# ProPrj___2025-11-13.net
KiCad netlist of a schematic drawn in EasyEDA Pro
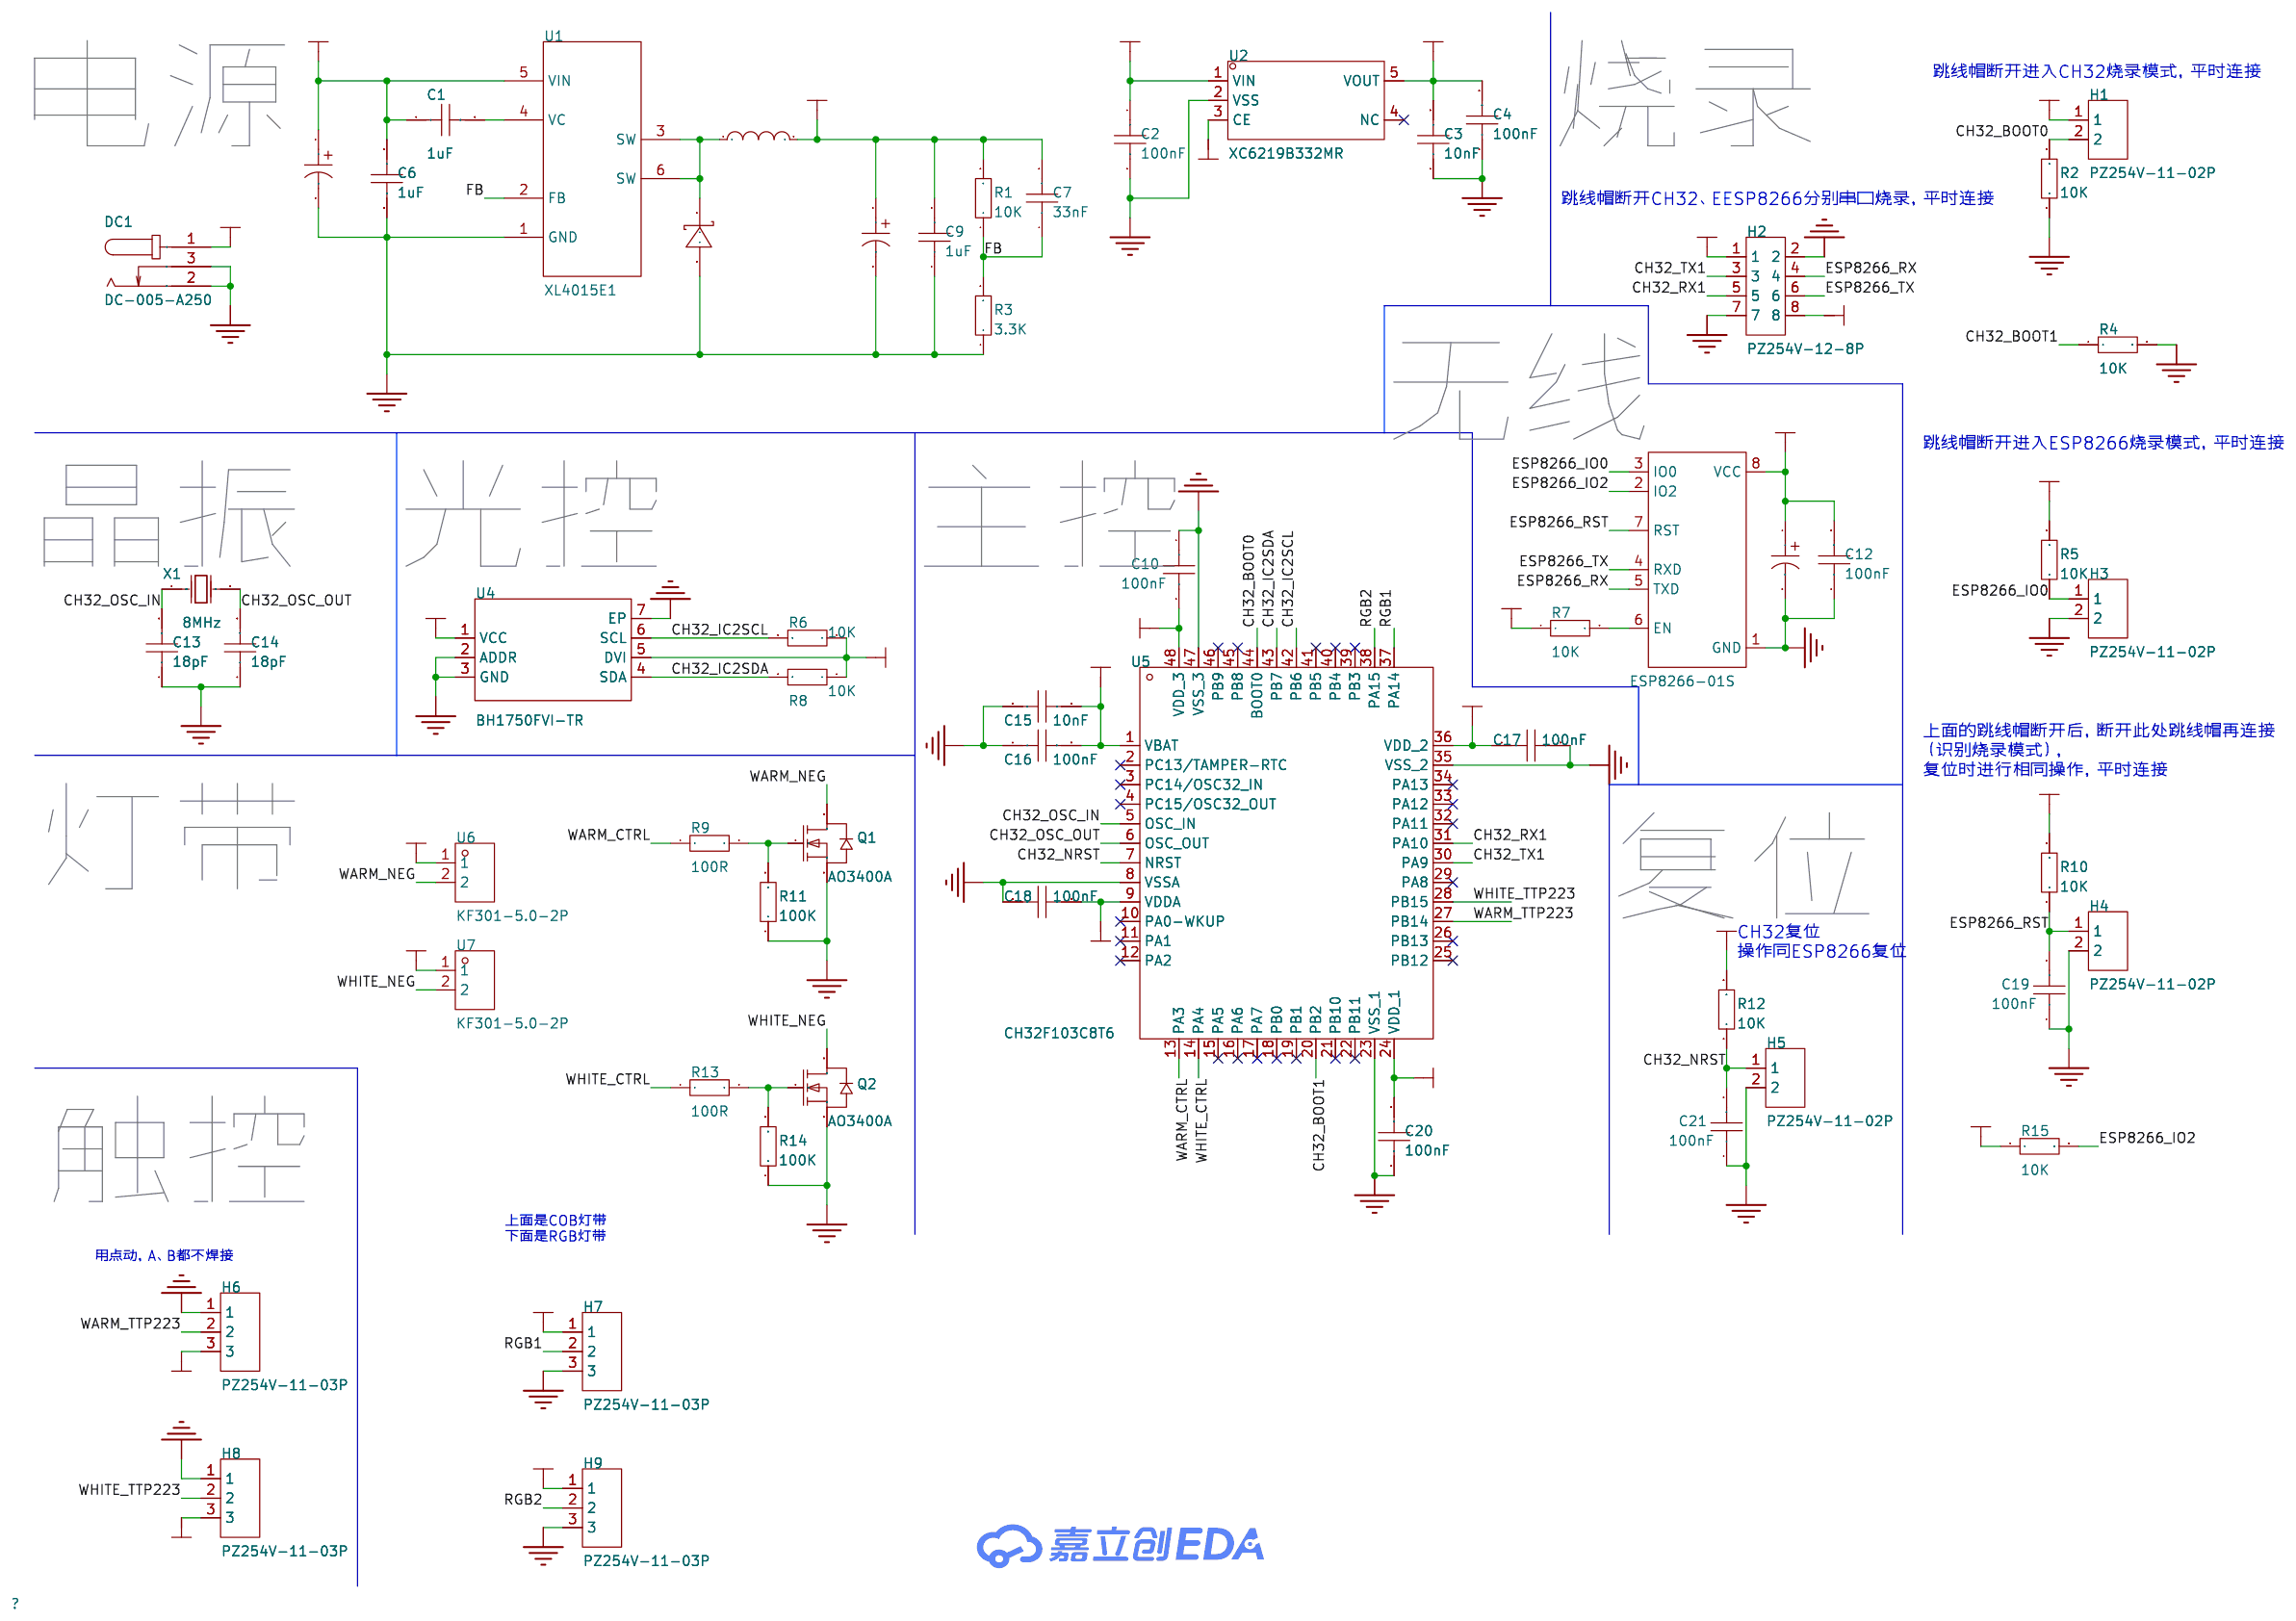
[diagram p0: schematic sheet]

(export (version "E")
  (design (tool "Eeschema 10.0.6"))
  (components
    (comp (ref "C1")
      (value "1uF")
      (footprint "easyedapro:C0805")
      (libsource (lib "easyedapro") (part "Capacitance"))
    )
    (comp (ref "C2")
      (value "100nF")
      (footprint "easyedapro:C0805")
      (libsource (lib "easyedapro") (part "Capacitance"))
    )
    (comp (ref "C3")
      (value "10nF")
      (footprint "easyedapro:C0805")
      (libsource (lib "easyedapro") (part "Capacitance"))
    )
    (comp (ref "C4")
      (value "100nF")
      (footprint "easyedapro:C0805")
      (libsource (lib "easyedapro") (part "Capacitance"))
    )
    (comp (ref "C5")
      (value "220uF")
      (footprint "easyedapro:贴片铝电解电容220uF_35V_8*10.5mm")
      (description "淘宝深圳市优信电子科技有限公司购买")
      (libsource (lib "easyedapro") (part "贴片铝电解电容220uF_35V_8*10.5mm"))
    )
    (comp (ref "C6")
      (value "1uF")
      (footprint "easyedapro:C0805")
      (libsource (lib "easyedapro") (part "Capacitance"))
    )
    (comp (ref "C7")
      (value "33nF")
      (footprint "easyedapro:C0805")
      (libsource (lib "easyedapro") (part "Capacitance"))
    )
    (comp (ref "C8")
      (value "470uF")
      (footprint "easyedapro:贴片铝电解电容470uF_10V_6.3*7.7mm")
      (description "淘宝深圳市优信电子科技有限公司购买")
      (libsource (lib "easyedapro") (part "贴片铝电解电容470uF_10V_6.3*7.7mm"))
    )
    (comp (ref "C9")
      (value "1uF")
      (footprint "easyedapro:C0805")
      (libsource (lib "easyedapro") (part "Capacitance"))
    )
    (comp (ref "C10")
      (value "100nF")
      (footprint "easyedapro:C0805")
      (libsource (lib "easyedapro") (part "Capacitance"))
    )
    (comp (ref "C11")
      (value "100uF")
      (footprint "easyedapro:贴片铝电解电容100uF_10V_5*5.4mm")
      (description "淘宝深圳市优信电子科技有限公司购买")
      (libsource (lib "easyedapro") (part "贴片铝电解电容100uF_10V_5*5.4mm"))
    )
    (comp (ref "C12")
      (value "100nF")
      (footprint "easyedapro:C0805")
      (libsource (lib "easyedapro") (part "Capacitance"))
    )
    (comp (ref "C13")
      (value "18pF")
      (footprint "easyedapro:C0805")
      (libsource (lib "easyedapro") (part "Capacitance"))
    )
    (comp (ref "C14")
      (value "18pF")
      (footprint "easyedapro:C0805")
      (libsource (lib "easyedapro") (part "Capacitance"))
    )
    (comp (ref "C15")
      (value "10nF")
      (footprint "easyedapro:C0805")
      (libsource (lib "easyedapro") (part "Capacitance"))
    )
    (comp (ref "C16")
      (value "100nF")
      (footprint "easyedapro:C0805")
      (libsource (lib "easyedapro") (part "Capacitance"))
    )
    (comp (ref "C17")
      (value "100nF")
      (footprint "easyedapro:C0805")
      (libsource (lib "easyedapro") (part "Capacitance"))
    )
    (comp (ref "C18")
      (value "100nF")
      (footprint "easyedapro:C0805")
      (libsource (lib "easyedapro") (part "Capacitance"))
    )
    (comp (ref "C19")
      (value "100nF")
      (footprint "easyedapro:C0805")
      (libsource (lib "easyedapro") (part "Capacitance"))
    )
    (comp (ref "C20")
      (value "100nF")
      (footprint "easyedapro:C0805")
      (libsource (lib "easyedapro") (part "Capacitance"))
    )
    (comp (ref "C21")
      (value "100nF")
      (footprint "easyedapro:C0805")
      (libsource (lib "easyedapro") (part "Capacitance"))
    )
    (comp (ref "D1")
      (value "SS54")
      (footprint "easyedapro:SS54SMB40V5AD0-214")
      (description "淘宝优信电子购买")
      (libsource (lib "easyedapro") (part "SS54SMB40V5AD0-214"))
    )
    (comp (ref "DC1")
      (value "DC-005-A250")
      (footprint "easyedapro:DC-IN-TH_DC-005-A250")
      (description "连接器类型:DC电源插座;安装方式:弯插;触点内径:2.5mm;触点外径:6.3mm;额定电流:3A;额定电压:30V;工作温度范围:-20°C~+70°C;")
      (fields (field (name "Manufacturer") "XUNPU(讯普)"))
      (libsource (lib "easyedapro") (part "DC-005-A250"))
    )
    (comp (ref "H1")
      (value "PZ254V-11-02P")
      (footprint "easyedapro:HDR-TH_2P-P2.54-V-M")
      (fields (field (name "Manufacturer") "XFCN(兴飞)"))
      (libsource (lib "easyedapro") (part "PZ254V-11-02P"))
    )
    (comp (ref "H2")
      (value "PZ254V-12-8P")
      (footprint "easyedapro:HDR-TH_8P-P2.54-V-M-R2-C4-S2.54")
      (fields (field (name "Manufacturer") "XFCN(兴飞)"))
      (libsource (lib "easyedapro") (part "PZ254V-12-8P"))
    )
    (comp (ref "H3")
      (value "PZ254V-11-02P")
      (footprint "easyedapro:HDR-TH_2P-P2.54-V-M")
      (fields (field (name "Manufacturer") "XFCN(兴飞)"))
      (libsource (lib "easyedapro") (part "PZ254V-11-02P"))
    )
    (comp (ref "H4")
      (value "PZ254V-11-02P")
      (footprint "easyedapro:HDR-TH_2P-P2.54-V-M")
      (fields (field (name "Manufacturer") "XFCN(兴飞)"))
      (libsource (lib "easyedapro") (part "PZ254V-11-02P"))
    )
    (comp (ref "H5")
      (value "PZ254V-11-02P")
      (footprint "easyedapro:HDR-TH_2P-P2.54-V-M")
      (fields (field (name "Manufacturer") "XFCN(兴飞)"))
      (libsource (lib "easyedapro") (part "PZ254V-11-02P"))
    )
    (comp (ref "H6")
      (value "PZ254V-11-03P")
      (footprint "easyedapro:HDR-TH_3P-P2.54-V-M")
      (fields (field (name "Manufacturer") "XFCN(兴飞)"))
      (libsource (lib "easyedapro") (part "PZ254V-11-03P_C2937625"))
    )
    (comp (ref "H7")
      (value "PZ254V-11-03P")
      (footprint "easyedapro:HDR-TH_3P-P2.54-V-M")
      (fields (field (name "Manufacturer") "XFCN(兴飞)"))
      (libsource (lib "easyedapro") (part "PZ254V-11-03P_C2937625"))
    )
    (comp (ref "H8")
      (value "PZ254V-11-03P")
      (footprint "easyedapro:HDR-TH_3P-P2.54-V-M")
      (fields (field (name "Manufacturer") "XFCN(兴飞)"))
      (libsource (lib "easyedapro") (part "PZ254V-11-03P_C2937625"))
    )
    (comp (ref "H9")
      (value "PZ254V-11-03P")
      (footprint "easyedapro:HDR-TH_3P-P2.54-V-M")
      (fields (field (name "Manufacturer") "XFCN(兴飞)"))
      (libsource (lib "easyedapro") (part "PZ254V-11-03P_C2937625"))
    )
    (comp (ref "L1")
      (value "68uH")
      (footprint "easyedapro:65125铁硅铝电感/68uH(1.0线)")
      (description "淘宝优信电子购买")
      (libsource (lib "easyedapro") (part "65125铁硅铝电感/68uH(1.0线)"))
    )
    (comp (ref "Q1")
      (value "AO3400A")
      (footprint "easyedapro:SOT-23-3_L2.9-W1.3-P1.90-LS2.4-BR")
      (fields (field (name "Manufacturer") "UMW(友台半导体)"))
      (libsource (lib "easyedapro") (part "AO3400A_C347475"))
    )
    (comp (ref "Q2")
      (value "AO3400A")
      (footprint "easyedapro:SOT-23-3_L2.9-W1.3-P1.90-LS2.4-BR")
      (fields (field (name "Manufacturer") "UMW(友台半导体)"))
      (libsource (lib "easyedapro") (part "AO3400A_C347475"))
    )
    (comp (ref "R1") (value "10K") (footprint "easyedapro:R0603") (libsource (lib "easyedapro") (part "电阻")))
    (comp (ref "R2") (value "10K") (footprint "easyedapro:R0603") (libsource (lib "easyedapro") (part "电阻")))
    (comp (ref "R3") (value "3.3K") (footprint "easyedapro:R0603") (libsource (lib "easyedapro") (part "电阻")))
    (comp (ref "R4") (value "10K") (footprint "easyedapro:R0603") (libsource (lib "easyedapro") (part "电阻")))
    (comp (ref "R5") (value "10K") (footprint "easyedapro:R0603") (libsource (lib "easyedapro") (part "电阻")))
    (comp (ref "R6") (value "10K") (footprint "easyedapro:R0603") (libsource (lib "easyedapro") (part "电阻")))
    (comp (ref "R7") (value "10K") (footprint "easyedapro:R0603") (libsource (lib "easyedapro") (part "电阻")))
    (comp (ref "R8") (value "10K") (footprint "easyedapro:R0603") (libsource (lib "easyedapro") (part "电阻")))
    (comp (ref "R9") (value "100R") (footprint "easyedapro:R0603") (libsource (lib "easyedapro") (part "电阻")))
    (comp (ref "R10") (value "10K") (footprint "easyedapro:R0603") (libsource (lib "easyedapro") (part "电阻")))
    (comp (ref "R11")
      (value "100K")
      (footprint "easyedapro:R0603")
      (libsource (lib "easyedapro") (part "电阻"))
    )
    (comp (ref "R12") (value "10K") (footprint "easyedapro:R0603") (libsource (lib "easyedapro") (part "电阻")))
    (comp (ref "R13")
      (value "100R")
      (footprint "easyedapro:R0603")
      (libsource (lib "easyedapro") (part "电阻"))
    )
    (comp (ref "R14")
      (value "100K")
      (footprint "easyedapro:R0603")
      (libsource (lib "easyedapro") (part "电阻"))
    )
    (comp (ref "R15") (value "10K") (footprint "easyedapro:R0603") (libsource (lib "easyedapro") (part "电阻")))
    (comp (ref "U1")
      (value "XL4015E1")
      (footprint "easyedapro:TO-263-5_L10.2-W8.9-P1.70-TL")
      (description "功能类型:降压型;工作电压:8V~36V;输出电压:1.25V~32V;输出电流:5A;输出类型:可调;")
      (fields (field (name "Manufacturer") "XLSEMI(芯龙)"))
      (libsource (lib "easyedapro") (part "XL4015E1"))
    )
    (comp (ref "U2")
      (value "XC6219B332MR")
      (footprint "easyedapro:SOT-23-5_L3.0-W1.7-P0.95-LS2.8-BR")
      (description "输出类型:固定;工作电压:7V;输出电压:3.3V;输出电流:300mA;电源纹波抑制比(PSRR):40dB@(1kHz);输出极性:正极;")
      (fields (field (name "Manufacturer") "UMW(友台半导体)"))
      (libsource (lib "easyedapro") (part "XC6219B332MR_C347386"))
    )
    (comp (ref "U3")
      (value "ESP8266-01S")
      (footprint "easyedapro:ESP8266ESP-01S")
      (description "淘宝深圳市优信电子科技有限公司购买")
      (libsource (lib "easyedapro") (part "ESP8266ESP-01S"))
    )
    (comp (ref "U4")
      (value "BH1750FVI-TR")
      (footprint "easyedapro:WSOF-6_L2.6-W1.6-P0.50-TL-EP")
      (description "检测颜色:-;接口类型:I2C;")
      (fields (field (name "Manufacturer") "ROHM(罗姆)"))
      (libsource (lib "easyedapro") (part "BH1750FVI-TR"))
    )
    (comp (ref "U5")
      (value "CH32F103C8T6")
      (footprint "easyedapro:LQFP-48_L7.0-W7.0-P0.50-LS9.0-BL")
      (description "CPU内核:ARM-M3;程序存储容量:64KB;RAM总容量:20KB;GPIO端口数量:37;工作电压范围:2.7V~5.5V;CPU最大主频:72MHz;程序存储器类型:-;应用领域:-;")
      (fields (field (name "Manufacturer") "WCH(南京沁恒)"))
      (libsource (lib "easyedapro") (part "CH32F103C8T6"))
    )
    (comp (ref "U6")
      (value "KF301-5.0-2P")
      (footprint "easyedapro:CONN-TH_P5.00_KF301-5.0-2P")
      (fields (field (name "Manufacturer") "KEFA(科发)"))
      (libsource (lib "easyedapro") (part "KF301-5.0-2P"))
    )
    (comp (ref "U7")
      (value "KF301-5.0-2P")
      (footprint "easyedapro:CONN-TH_P5.00_KF301-5.0-2P")
      (fields (field (name "Manufacturer") "KEFA(科发)"))
      (libsource (lib "easyedapro") (part "KF301-5.0-2P"))
    )
    (comp (ref "X1")
      (value "8MHz")
      (footprint "easyedapro:CRYSTAL-SMD_L5.0-W3.2")
      (description "晶振类型:贴片晶振;频率:8MHz;常温频差:±10ppm;负载电容:20pF;频率稳定度:±20ppm;")
      (fields (field (name "Manufacturer Part") "X50328MSB2GI") (field (name "Manufacturer") "YXC(扬兴晶振)"))
      (libsource (lib "easyedapro") (part "X50328MSB2GI"))
    )
  )
  (nets
    (net (code "1") (name "/CH32_BOOT0") (class "Default")
      (node (ref "H1") (pin "2") (pinfunction "2_2") (pintype "unspecified"))
      (node (ref "R2") (pin "2") (pinfunction "2_2") (pintype "input"))
      (node (ref "U5") (pin "44") (pinfunction "BOOT0_44") (pintype "unspecified"))
    )
    (net (code "2") (name "/CH32_BOOT1") (class "Default")
      (node (ref "R4") (pin "1") (pinfunction "1_1") (pintype "input"))
      (node (ref "U5") (pin "20") (pinfunction "PB2_20") (pintype "unspecified"))
    )
    (net (code "3") (name "/CH32_IC2SCL") (class "Default")
      (node (ref "R6") (pin "2") (pinfunction "2_2") (pintype "input"))
      (node (ref "U4") (pin "6") (pinfunction "SCL_6") (pintype "unspecified"))
      (node (ref "U5") (pin "42") (pinfunction "PB6_42") (pintype "unspecified"))
    )
    (net (code "4") (name "/CH32_IC2SDA") (class "Default")
      (node (ref "R8") (pin "2") (pinfunction "2_2") (pintype "input"))
      (node (ref "U4") (pin "4") (pinfunction "SDA_4") (pintype "unspecified"))
      (node (ref "U5") (pin "43") (pinfunction "PB7_43") (pintype "unspecified"))
    )
    (net (code "5") (name "/CH32_NRST") (class "Default")
      (node (ref "C21") (pin "2") (pinfunction "2_2") (pintype "input"))
      (node (ref "H5") (pin "1") (pinfunction "1_1") (pintype "unspecified"))
      (node (ref "R12") (pin "1") (pinfunction "1_1") (pintype "input"))
      (node (ref "U5") (pin "7") (pinfunction "NRST_7") (pintype "unspecified"))
    )
    (net (code "6") (name "/CH32_OSC_IN") (class "Default")
      (node (ref "C13") (pin "2") (pinfunction "2_2") (pintype "input"))
      (node (ref "U5") (pin "5") (pinfunction "OSC_IN_5") (pintype "unspecified"))
      (node (ref "X1") (pin "1") (pinfunction "OSC1_1") (pintype "input"))
    )
    (net (code "7") (name "/CH32_OSC_OUT") (class "Default")
      (node (ref "C14") (pin "2") (pinfunction "2_2") (pintype "input"))
      (node (ref "U5") (pin "6") (pinfunction "OSC_OUT_6") (pintype "unspecified"))
      (node (ref "X1") (pin "2") (pinfunction "OSC2_2") (pintype "input"))
    )
    (net (code "8") (name "/CH32_RX1") (class "Default")
      (node (ref "H2") (pin "5") (pinfunction "5_5") (pintype "unspecified"))
      (node (ref "U5") (pin "31") (pinfunction "PA10_31") (pintype "unspecified"))
    )
    (net (code "9") (name "/CH32_TX1") (class "Default")
      (node (ref "H2") (pin "3") (pinfunction "3_3") (pintype "unspecified"))
      (node (ref "U5") (pin "30") (pinfunction "PA9_30") (pintype "unspecified"))
    )
    (net (code "10") (name "/ESP8266_IO0") (class "Default")
      (node (ref "H3") (pin "1") (pinfunction "1_1") (pintype "unspecified"))
      (node (ref "R5") (pin "1") (pinfunction "1_1") (pintype "input"))
      (node (ref "U3") (pin "3") (pinfunction "IO0_3") (pintype "unspecified"))
    )
    (net (code "11") (name "/ESP8266_IO2") (class "Default")
      (node (ref "R15") (pin "2") (pinfunction "2_2") (pintype "input"))
      (node (ref "U3") (pin "2") (pinfunction "IO2_2") (pintype "unspecified"))
    )
    (net (code "12") (name "/ESP8266_RST") (class "Default")
      (node (ref "C19") (pin "2") (pinfunction "2_2") (pintype "input"))
      (node (ref "H4") (pin "1") (pinfunction "1_1") (pintype "unspecified"))
      (node (ref "R10") (pin "1") (pinfunction "1_1") (pintype "input"))
      (node (ref "U3") (pin "7") (pinfunction "RST_7") (pintype "unspecified"))
    )
    (net (code "13") (name "/ESP8266_RX") (class "Default")
      (node (ref "H2") (pin "4") (pinfunction "4_4") (pintype "unspecified"))
      (node (ref "U3") (pin "5") (pinfunction "TXD_5") (pintype "unspecified"))
    )
    (net (code "14") (name "/ESP8266_TX") (class "Default")
      (node (ref "H2") (pin "6") (pinfunction "6_6") (pintype "unspecified"))
      (node (ref "U3") (pin "4") (pinfunction "RXD_4") (pintype "unspecified"))
    )
    (net (code "15") (name "/FB") (class "Default")
      (node (ref "C7") (pin "1") (pinfunction "1_1") (pintype "input"))
      (node (ref "R1") (pin "1") (pinfunction "1_1") (pintype "input"))
      (node (ref "R3") (pin "2") (pinfunction "2_2") (pintype "input"))
      (node (ref "U1") (pin "2") (pinfunction "FB_2") (pintype "unspecified"))
    )
    (net (code "16") (name "/RGB1") (class "Default")
      (node (ref "H7") (pin "2") (pinfunction "2_2") (pintype "unspecified"))
      (node (ref "U5") (pin "37") (pinfunction "PA14_37") (pintype "unspecified"))
    )
    (net (code "17") (name "/RGB2") (class "Default")
      (node (ref "H9") (pin "2") (pinfunction "2_2") (pintype "unspecified"))
      (node (ref "U5") (pin "38") (pinfunction "PA15_38") (pintype "unspecified"))
    )
    (net (code "18") (name "/WARM_CTRL") (class "Default")
      (node (ref "R9") (pin "1") (pinfunction "1_1") (pintype "input"))
      (node (ref "U5") (pin "13") (pinfunction "PA3_13") (pintype "unspecified"))
    )
    (net (code "19") (name "/WARM_NEG") (class "Default")
      (node (ref "Q1") (pin "3") (pinfunction "D_3") (pintype "unspecified"))
      (node (ref "U6") (pin "2") (pinfunction "2_2") (pintype "unspecified"))
    )
    (net (code "20") (name "/WARM_TTP223") (class "Default")
      (node (ref "H6") (pin "2") (pinfunction "2_2") (pintype "unspecified"))
      (node (ref "U5") (pin "27") (pinfunction "PB14_27") (pintype "unspecified"))
    )
    (net (code "21") (name "/WHITE_CTRL") (class "Default")
      (node (ref "R13") (pin "1") (pinfunction "1_1") (pintype "input"))
      (node (ref "U5") (pin "14") (pinfunction "PA4_14") (pintype "unspecified"))
    )
    (net (code "22") (name "/WHITE_NEG") (class "Default")
      (node (ref "Q2") (pin "3") (pinfunction "D_3") (pintype "unspecified"))
      (node (ref "U7") (pin "2") (pinfunction "2_2") (pintype "unspecified"))
    )
    (net (code "23") (name "/WHITE_TTP223") (class "Default")
      (node (ref "H8") (pin "2") (pinfunction "2_2") (pintype "unspecified"))
      (node (ref "U5") (pin "28") (pinfunction "PB15_28") (pintype "unspecified"))
    )
    (net (code "24") (name "3.3V") (class "Default")
      (node (ref "C10") (pin "2") (pinfunction "2_2") (pintype "input"))
      (node (ref "C11") (pin "1") (pinfunction "1_1") (pintype "input"))
      (node (ref "C12") (pin "2") (pinfunction "2_2") (pintype "input"))
      (node (ref "C15") (pin "2") (pinfunction "2_2") (pintype "input"))
      (node (ref "C16") (pin "2") (pinfunction "2_2") (pintype "input"))
      (node (ref "C17") (pin "1") (pinfunction "1_1") (pintype "input"))
      (node (ref "C18") (pin "2") (pinfunction "2_2") (pintype "input"))
      (node (ref "C20") (pin "2") (pinfunction "2_2") (pintype "input"))
      (node (ref "C3") (pin "2") (pinfunction "2_2") (pintype "input"))
      (node (ref "C4") (pin "2") (pinfunction "2_2") (pintype "input"))
      (node (ref "H1") (pin "1") (pinfunction "1_1") (pintype "unspecified"))
      (node (ref "H2") (pin "1") (pinfunction "1_1") (pintype "unspecified"))
      (node (ref "H2") (pin "8") (pinfunction "8_8") (pintype "unspecified"))
      (node (ref "H6") (pin "3") (pinfunction "3_3") (pintype "unspecified"))
      (node (ref "H8") (pin "3") (pinfunction "3_3") (pintype "unspecified"))
      (node (ref "R10") (pin "2") (pinfunction "2_2") (pintype "input"))
      (node (ref "R12") (pin "2") (pinfunction "2_2") (pintype "input"))
      (node (ref "R15") (pin "1") (pinfunction "1_1") (pintype "input"))
      (node (ref "R5") (pin "2") (pinfunction "2_2") (pintype "input"))
      (node (ref "R6") (pin "1") (pinfunction "1_1") (pintype "input"))
      (node (ref "R7") (pin "1") (pinfunction "1_1") (pintype "input"))
      (node (ref "R8") (pin "1") (pinfunction "1_1") (pintype "input"))
      (node (ref "U2") (pin "5") (pinfunction "VOUT_5") (pintype "unspecified"))
      (node (ref "U3") (pin "8") (pinfunction "VCC_8") (pintype "unspecified"))
      (node (ref "U4") (pin "1") (pinfunction "VCC_1") (pintype "unspecified"))
      (node (ref "U4") (pin "5") (pinfunction "DVI_5") (pintype "unspecified"))
      (node (ref "U5") (pin "1") (pinfunction "VBAT_1") (pintype "unspecified"))
      (node (ref "U5") (pin "24") (pinfunction "VDD_1_24") (pintype "unspecified"))
      (node (ref "U5") (pin "36") (pinfunction "VDD_2_36") (pintype "unspecified"))
      (node (ref "U5") (pin "48") (pinfunction "VDD_3_48") (pintype "unspecified"))
      (node (ref "U5") (pin "9") (pinfunction "VDDA_9") (pintype "unspecified"))
    )
    (net (code "25") (name "5V") (class "Default")
      (node (ref "C2") (pin "1") (pinfunction "1_1") (pintype "input"))
      (node (ref "C7") (pin "2") (pinfunction "2_2") (pintype "input"))
      (node (ref "C8") (pin "1") (pinfunction "1_1") (pintype "input"))
      (node (ref "C9") (pin "2") (pinfunction "2_2") (pintype "input"))
      (node (ref "H7") (pin "1") (pinfunction "1_1") (pintype "unspecified"))
      (node (ref "H9") (pin "1") (pinfunction "1_1") (pintype "unspecified"))
      (node (ref "L1") (pin "2") (pinfunction "2_2") (pintype "unspecified"))
      (node (ref "R1") (pin "2") (pinfunction "2_2") (pintype "input"))
      (node (ref "U2") (pin "1") (pinfunction "VIN_1") (pintype "unspecified"))
      (node (ref "U2") (pin "3") (pinfunction "CE_3") (pintype "unspecified"))
    )
    (net (code "26") (name "24V") (class "Default")
      (node (ref "C1") (pin "1") (pinfunction "1_1") (pintype "input"))
      (node (ref "C5") (pin "1") (pinfunction "1_1") (pintype "input"))
      (node (ref "C6") (pin "1") (pinfunction "1_1") (pintype "input"))
      (node (ref "DC1") (pin "1") (pinfunction "1_1") (pintype "input"))
      (node (ref "U1") (pin "5") (pinfunction "VIN_5") (pintype "unspecified"))
      (node (ref "U6") (pin "1") (pinfunction "1_1") (pintype "unspecified"))
      (node (ref "U7") (pin "1") (pinfunction "1_1") (pintype "unspecified"))
    )
    (net (code "27") (name "GND") (class "Default")
      (node (ref "C10") (pin "1") (pinfunction "1_1") (pintype "input"))
      (node (ref "C11") (pin "2") (pinfunction "2_2") (pintype "input"))
      (node (ref "C12") (pin "1") (pinfunction "1_1") (pintype "input"))
      (node (ref "C13") (pin "1") (pinfunction "1_1") (pintype "input"))
      (node (ref "C14") (pin "1") (pinfunction "1_1") (pintype "input"))
      (node (ref "C15") (pin "1") (pinfunction "1_1") (pintype "input"))
      (node (ref "C16") (pin "1") (pinfunction "1_1") (pintype "input"))
      (node (ref "C17") (pin "2") (pinfunction "2_2") (pintype "input"))
      (node (ref "C18") (pin "1") (pinfunction "1_1") (pintype "input"))
      (node (ref "C19") (pin "1") (pinfunction "1_1") (pintype "input"))
      (node (ref "C2") (pin "2") (pinfunction "2_2") (pintype "input"))
      (node (ref "C20") (pin "1") (pinfunction "1_1") (pintype "input"))
      (node (ref "C21") (pin "1") (pinfunction "1_1") (pintype "input"))
      (node (ref "C3") (pin "1") (pinfunction "1_1") (pintype "input"))
      (node (ref "C4") (pin "1") (pinfunction "1_1") (pintype "input"))
      (node (ref "C5") (pin "2") (pinfunction "2_2") (pintype "input"))
      (node (ref "C6") (pin "2") (pinfunction "2_2") (pintype "input"))
      (node (ref "C8") (pin "2") (pinfunction "2_2") (pintype "input"))
      (node (ref "C9") (pin "1") (pinfunction "1_1") (pintype "input"))
      (node (ref "D1") (pin "2") (pinfunction "A_2") (pintype "unspecified"))
      (node (ref "DC1") (pin "2") (pinfunction "2_2") (pintype "input"))
      (node (ref "DC1") (pin "3") (pinfunction "3_3") (pintype "input"))
      (node (ref "H2") (pin "2") (pinfunction "2_2") (pintype "unspecified"))
      (node (ref "H2") (pin "7") (pinfunction "7_7") (pintype "unspecified"))
      (node (ref "H3") (pin "2") (pinfunction "2_2") (pintype "unspecified"))
      (node (ref "H4") (pin "2") (pinfunction "2_2") (pintype "unspecified"))
      (node (ref "H5") (pin "2") (pinfunction "2_2") (pintype "unspecified"))
      (node (ref "H6") (pin "1") (pinfunction "1_1") (pintype "unspecified"))
      (node (ref "H7") (pin "3") (pinfunction "3_3") (pintype "unspecified"))
      (node (ref "H8") (pin "1") (pinfunction "1_1") (pintype "unspecified"))
      (node (ref "H9") (pin "3") (pinfunction "3_3") (pintype "unspecified"))
      (node (ref "Q1") (pin "2") (pinfunction "S_2") (pintype "unspecified"))
      (node (ref "Q2") (pin "2") (pinfunction "S_2") (pintype "unspecified"))
      (node (ref "R11") (pin "1") (pinfunction "1_1") (pintype "input"))
      (node (ref "R14") (pin "1") (pinfunction "1_1") (pintype "input"))
      (node (ref "R2") (pin "1") (pinfunction "1_1") (pintype "input"))
      (node (ref "R3") (pin "1") (pinfunction "1_1") (pintype "input"))
      (node (ref "R4") (pin "2") (pinfunction "2_2") (pintype "input"))
      (node (ref "U1") (pin "1") (pinfunction "GND_1") (pintype "unspecified"))
      (node (ref "U2") (pin "2") (pinfunction "VSS_2") (pintype "unspecified"))
      (node (ref "U3") (pin "1") (pinfunction "GND_1") (pintype "unspecified"))
      (node (ref "U4") (pin "2") (pinfunction "ADDR_2") (pintype "unspecified"))
      (node (ref "U4") (pin "3") (pinfunction "GND_3") (pintype "unspecified"))
      (node (ref "U4") (pin "7") (pinfunction "EP_7") (pintype "unspecified"))
      (node (ref "U5") (pin "23") (pinfunction "VSS_1_23") (pintype "unspecified"))
      (node (ref "U5") (pin "35") (pinfunction "VSS_2_35") (pintype "unspecified"))
      (node (ref "U5") (pin "47") (pinfunction "VSS_3_47") (pintype "unspecified"))
      (node (ref "U5") (pin "8") (pinfunction "VSSA_8") (pintype "unspecified"))
    )
    (net (code "28") (name "Net-(D1-K)") (class "Default")
      (node (ref "D1") (pin "1") (pinfunction "K_1") (pintype "unspecified"))
      (node (ref "L1") (pin "1") (pinfunction "1_1") (pintype "unspecified"))
      (node (ref "U1") (pin "3") (pinfunction "SW_3") (pintype "unspecified"))
      (node (ref "U1") (pin "6") (pinfunction "SW_6") (pintype "unspecified"))
    )
    (net (code "29") (name "Net-(Q1-G)") (class "Default")
      (node (ref "Q1") (pin "1") (pinfunction "G_1") (pintype "unspecified"))
      (node (ref "R11") (pin "2") (pinfunction "2_2") (pintype "input"))
      (node (ref "R9") (pin "2") (pinfunction "2_2") (pintype "input"))
    )
    (net (code "30") (name "Net-(Q2-G)") (class "Default")
      (node (ref "Q2") (pin "1") (pinfunction "G_1") (pintype "unspecified"))
      (node (ref "R13") (pin "2") (pinfunction "2_2") (pintype "input"))
      (node (ref "R14") (pin "2") (pinfunction "2_2") (pintype "input"))
    )
    (net (code "31") (name "Net-(U1-VC)") (class "Default")
      (node (ref "C1") (pin "2") (pinfunction "2_2") (pintype "input"))
      (node (ref "U1") (pin "4") (pinfunction "VC_4") (pintype "unspecified"))
    )
    (net (code "32") (name "Net-(U3-EN)") (class "Default")
      (node (ref "R7") (pin "2") (pinfunction "2_2") (pintype "input"))
      (node (ref "U3") (pin "6") (pinfunction "EN_6") (pintype "unspecified"))
    )
    (net (code "33") (name "unconnected-(U2-NC-Pad4)") (class "Default")
      (node (ref "U2") (pin "4") (pinfunction "NC_4") (pintype "unspecified+no_connect"))
    )
    (net (code "34") (name "unconnected-(U5-PA0-WKUP-Pad10)") (class "Default")
      (node (ref "U5") (pin "10") (pinfunction "PA0-WKUP_10") (pintype "unspecified+no_connect"))
    )
    (net (code "35") (name "unconnected-(U5-PA1-Pad11)") (class "Default")
      (node (ref "U5") (pin "11") (pinfunction "PA1_11") (pintype "unspecified+no_connect"))
    )
    (net (code "36") (name "unconnected-(U5-PA2-Pad12)") (class "Default")
      (node (ref "U5") (pin "12") (pinfunction "PA2_12") (pintype "unspecified+no_connect"))
    )
    (net (code "37") (name "unconnected-(U5-PA5-Pad15)") (class "Default")
      (node (ref "U5") (pin "15") (pinfunction "PA5_15") (pintype "unspecified+no_connect"))
    )
    (net (code "38") (name "unconnected-(U5-PA6-Pad16)") (class "Default")
      (node (ref "U5") (pin "16") (pinfunction "PA6_16") (pintype "unspecified+no_connect"))
    )
    (net (code "39") (name "unconnected-(U5-PA7-Pad17)") (class "Default")
      (node (ref "U5") (pin "17") (pinfunction "PA7_17") (pintype "unspecified+no_connect"))
    )
    (net (code "40") (name "unconnected-(U5-PA8-Pad29)") (class "Default")
      (node (ref "U5") (pin "29") (pinfunction "PA8_29") (pintype "unspecified+no_connect"))
    )
    (net (code "41") (name "unconnected-(U5-PA11-Pad32)") (class "Default")
      (node (ref "U5") (pin "32") (pinfunction "PA11_32") (pintype "unspecified+no_connect"))
    )
    (net (code "42") (name "unconnected-(U5-PA12-Pad33)") (class "Default")
      (node (ref "U5") (pin "33") (pinfunction "PA12_33") (pintype "unspecified+no_connect"))
    )
    (net (code "43") (name "unconnected-(U5-PA13-Pad34)") (class "Default")
      (node (ref "U5") (pin "34") (pinfunction "PA13_34") (pintype "unspecified+no_connect"))
    )
    (net (code "44") (name "unconnected-(U5-PB0-Pad18)") (class "Default")
      (node (ref "U5") (pin "18") (pinfunction "PB0_18") (pintype "unspecified+no_connect"))
    )
    (net (code "45") (name "unconnected-(U5-PB1-Pad19)") (class "Default")
      (node (ref "U5") (pin "19") (pinfunction "PB1_19") (pintype "unspecified+no_connect"))
    )
    (net (code "46") (name "unconnected-(U5-PB3-Pad39)") (class "Default")
      (node (ref "U5") (pin "39") (pinfunction "PB3_39") (pintype "unspecified+no_connect"))
    )
    (net (code "47") (name "unconnected-(U5-PB4-Pad40)") (class "Default")
      (node (ref "U5") (pin "40") (pinfunction "PB4_40") (pintype "unspecified+no_connect"))
    )
    (net (code "48") (name "unconnected-(U5-PB5-Pad41)") (class "Default")
      (node (ref "U5") (pin "41") (pinfunction "PB5_41") (pintype "unspecified+no_connect"))
    )
    (net (code "49") (name "unconnected-(U5-PB8-Pad45)") (class "Default")
      (node (ref "U5") (pin "45") (pinfunction "PB8_45") (pintype "unspecified+no_connect"))
    )
    (net (code "50") (name "unconnected-(U5-PB9-Pad46)") (class "Default")
      (node (ref "U5") (pin "46") (pinfunction "PB9_46") (pintype "unspecified+no_connect"))
    )
    (net (code "51") (name "unconnected-(U5-PB10-Pad21)") (class "Default")
      (node (ref "U5") (pin "21") (pinfunction "PB10_21") (pintype "unspecified+no_connect"))
    )
    (net (code "52") (name "unconnected-(U5-PB11-Pad22)") (class "Default")
      (node (ref "U5") (pin "22") (pinfunction "PB11_22") (pintype "unspecified+no_connect"))
    )
    (net (code "53") (name "unconnected-(U5-PB12-Pad25)") (class "Default")
      (node (ref "U5") (pin "25") (pinfunction "PB12_25") (pintype "unspecified+no_connect"))
    )
    (net (code "54") (name "unconnected-(U5-PB13-Pad26)") (class "Default")
      (node (ref "U5") (pin "26") (pinfunction "PB13_26") (pintype "unspecified+no_connect"))
    )
    (net (code "55") (name "unconnected-(U5-PC13{slash}TAMPER-RTC-Pad2)") (class "Default")
      (node (ref "U5") (pin "2") (pinfunction "PC13/TAMPER-RTC_2") (pintype "unspecified+no_connect"))
    )
    (net (code "56") (name "unconnected-(U5-PC14{slash}OSC32_IN-Pad3)") (class "Default")
      (node (ref "U5") (pin "3") (pinfunction "PC14/OSC32_IN_3") (pintype "unspecified+no_connect"))
    )
    (net (code "57") (name "unconnected-(U5-PC15{slash}OSC32_OUT-Pad4)") (class "Default")
      (node (ref "U5") (pin "4") (pinfunction "PC15/OSC32_OUT_4") (pintype "unspecified+no_connect"))
    )
  )
)
